# Sheet4.net
KiCad netlist of a schematic drawn in Altium Designer
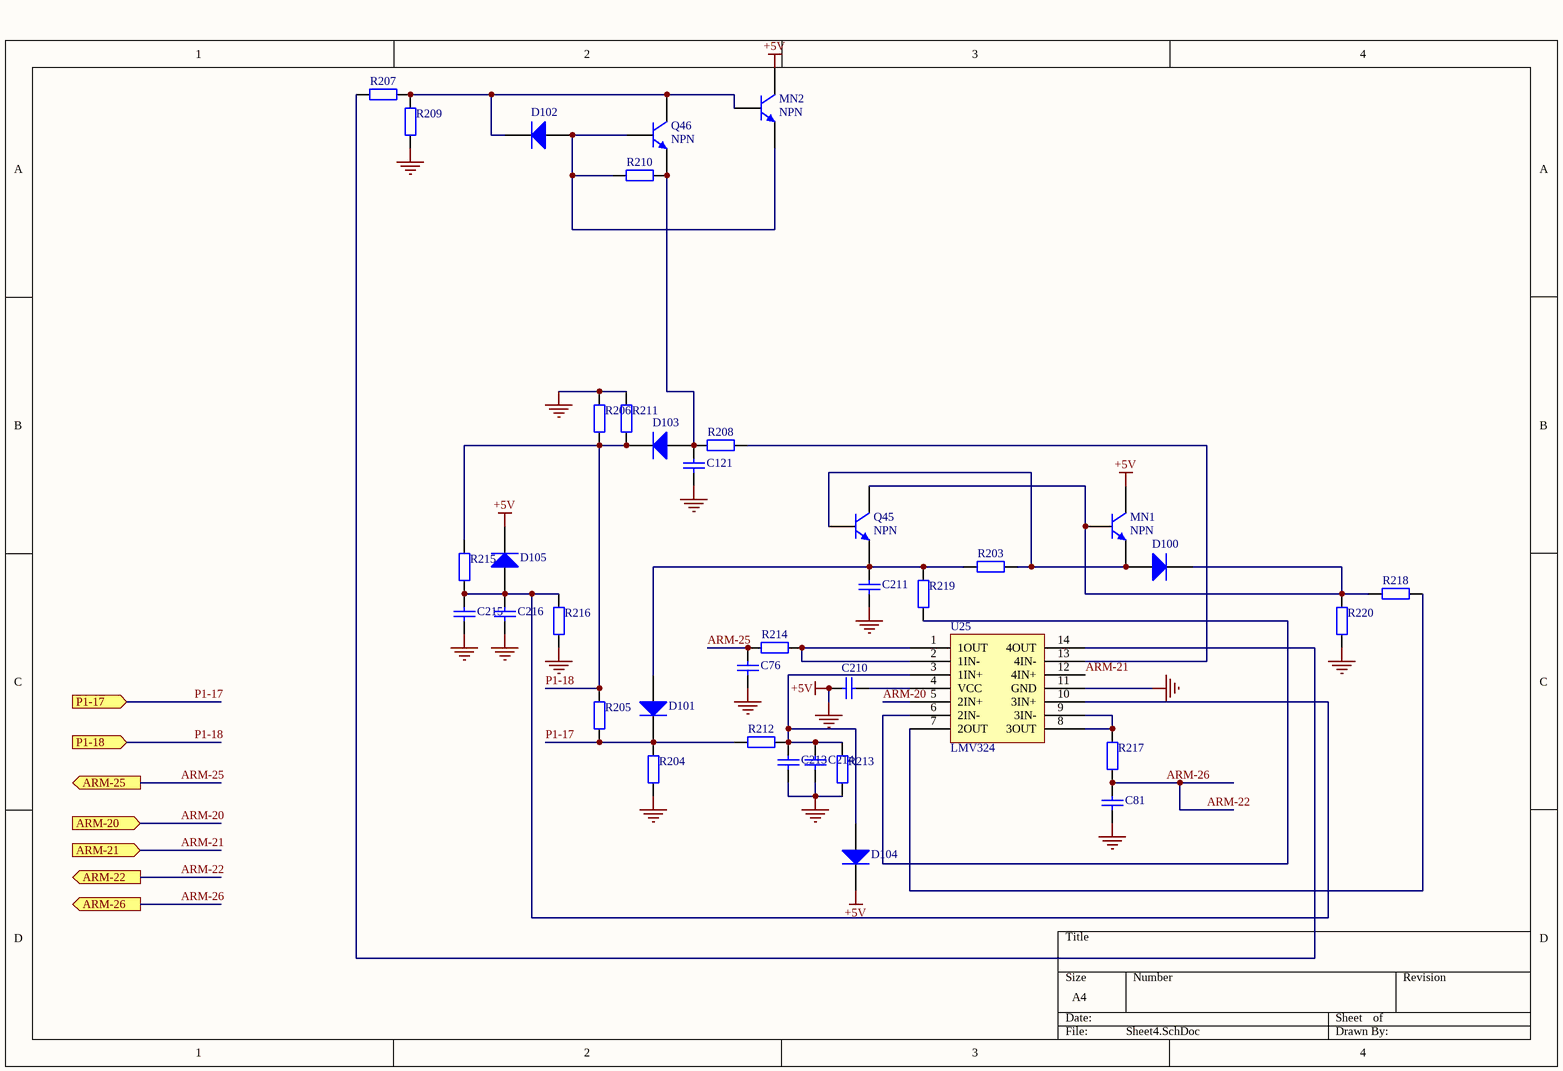
[diagram p0: Sheet4.SchDoc]

(export (version "E")
  (design (tool "Eeschema 10.0.6"))
  (components
    (comp (ref "C76")
      (value "Cap")
      (footprint "RAD-0.3")
      (description "Capacitor")
      (fields (field (name "PUBLISHER") "Altium Limited"))
      (libsource (lib "Miscellaneous Devices") (part "Cap"))
    )
    (comp (ref "C81")
      (value "Cap")
      (footprint "RAD-0.3")
      (description "Capacitor")
      (fields (field (name "PUBLISHER") "Altium Limited"))
      (libsource (lib "Miscellaneous Devices") (part "Cap"))
    )
    (comp (ref "C121")
      (value "Cap")
      (footprint "RAD-0.3")
      (description "Capacitor")
      (fields (field (name "PUBLISHER") "Altium Limited"))
      (libsource (lib "Miscellaneous Devices") (part "Cap"))
    )
    (comp (ref "C210")
      (value "Cap")
      (footprint "RAD-0.3")
      (description "Capacitor")
      (fields (field (name "PUBLISHER") "Altium Limited"))
      (libsource (lib "Miscellaneous Devices") (part "Cap"))
    )
    (comp (ref "C211")
      (value "Cap")
      (footprint "RAD-0.3")
      (description "Capacitor")
      (fields (field (name "PUBLISHER") "Altium Limited"))
      (libsource (lib "Miscellaneous Devices") (part "Cap"))
    )
    (comp (ref "C213")
      (value "Cap")
      (footprint "RAD-0.3")
      (description "Capacitor")
      (fields (field (name "PUBLISHER") "Altium Limited"))
      (libsource (lib "Miscellaneous Devices") (part "Cap"))
    )
    (comp (ref "C214")
      (value "Cap")
      (footprint "RAD-0.3")
      (description "Capacitor")
      (fields (field (name "PUBLISHER") "Altium Limited"))
      (libsource (lib "Miscellaneous Devices") (part "Cap"))
    )
    (comp (ref "C215")
      (value "Cap")
      (footprint "RAD-0.3")
      (description "Capacitor")
      (fields (field (name "PUBLISHER") "Altium Limited"))
      (libsource (lib "Miscellaneous Devices") (part "Cap"))
    )
    (comp (ref "C216")
      (value "Cap")
      (footprint "RAD-0.3")
      (description "Capacitor")
      (fields (field (name "PUBLISHER") "Altium Limited"))
      (libsource (lib "Miscellaneous Devices") (part "Cap"))
    )
    (comp (ref "D100")
      (value "Diode 1N4007")
      (footprint "DO-41")
      (description "1 Amp General Purpose Rectifier")
      (fields (field (name "PUBLISHER") "Altium Limited"))
      (libsource (lib "Miscellaneous Devices") (part "Diode 1N4007"))
    )
    (comp (ref "D101")
      (value "Diode 1N4007")
      (footprint "DO-41")
      (description "1 Amp General Purpose Rectifier")
      (fields (field (name "PUBLISHER") "Altium Limited"))
      (libsource (lib "Miscellaneous Devices") (part "Diode 1N4007"))
    )
    (comp (ref "D102")
      (value "Diode 1N4007")
      (footprint "DO-41")
      (description "1 Amp General Purpose Rectifier")
      (fields (field (name "PUBLISHER") "Altium Limited"))
      (libsource (lib "Miscellaneous Devices") (part "Diode 1N4007"))
    )
    (comp (ref "D103")
      (value "Diode 1N4007")
      (footprint "DO-41")
      (description "1 Amp General Purpose Rectifier")
      (fields (field (name "PUBLISHER") "Altium Limited"))
      (libsource (lib "Miscellaneous Devices") (part "Diode 1N4007"))
    )
    (comp (ref "D104")
      (value "Diode 1N4007")
      (footprint "DO-41")
      (description "1 Amp General Purpose Rectifier")
      (fields (field (name "PUBLISHER") "Altium Limited"))
      (libsource (lib "Miscellaneous Devices") (part "Diode 1N4007"))
    )
    (comp (ref "D105")
      (value "Diode 1N4007")
      (footprint "DO-41")
      (description "1 Amp General Purpose Rectifier")
      (fields (field (name "PUBLISHER") "Altium Limited"))
      (libsource (lib "Miscellaneous Devices") (part "Diode 1N4007"))
    )
    (comp (ref "MN1")
      (value "NPN")
      (footprint "TO-226")
      (description "NPN Bipolar Transistor")
      (fields (field (name "PUBLISHER") "Altium Limited"))
      (libsource (lib "Miscellaneous Devices") (part "NPN"))
    )
    (comp (ref "MN2")
      (value "NPN")
      (footprint "TO-226")
      (description "NPN Bipolar Transistor")
      (fields (field (name "PUBLISHER") "Altium Limited"))
      (libsource (lib "Miscellaneous Devices") (part "NPN"))
    )
    (comp (ref "Q45")
      (value "NPN")
      (footprint "TO-226")
      (description "NPN Bipolar Transistor")
      (fields (field (name "PUBLISHER") "Altium Limited"))
      (libsource (lib "Miscellaneous Devices") (part "NPN"))
    )
    (comp (ref "Q46")
      (value "NPN")
      (footprint "TO-226")
      (description "NPN Bipolar Transistor")
      (fields (field (name "PUBLISHER") "Altium Limited"))
      (libsource (lib "Miscellaneous Devices") (part "NPN"))
    )
    (comp (ref "R203")
      (value "Res2")
      (footprint "AXIAL-0.4")
      (description "Resistor")
      (fields (field (name "PUBLISHER") "Altium Limited"))
      (libsource (lib "") (part "Res2_2"))
    )
    (comp (ref "R204")
      (value "Res2")
      (footprint "AXIAL-0.4")
      (description "Resistor")
      (fields (field (name "PUBLISHER") "Altium Limited"))
      (libsource (lib "Miscellaneous Devices") (part "Res2"))
    )
    (comp (ref "R205")
      (value "Res2")
      (footprint "AXIAL-0.4")
      (description "Resistor")
      (fields (field (name "PUBLISHER") "Altium Limited"))
      (libsource (lib "Miscellaneous Devices") (part "Res2"))
    )
    (comp (ref "R206")
      (value "Res2")
      (footprint "AXIAL-0.4")
      (description "Resistor")
      (fields (field (name "PUBLISHER") "Altium Limited"))
      (libsource (lib "Miscellaneous Devices") (part "Res2"))
    )
    (comp (ref "R207")
      (value "Res2")
      (footprint "AXIAL-0.4")
      (description "Resistor")
      (fields (field (name "PUBLISHER") "Altium Limited"))
      (libsource (lib "") (part "Res2_3"))
    )
    (comp (ref "R208")
      (value "Res2")
      (footprint "AXIAL-0.4")
      (description "Resistor")
      (fields (field (name "PUBLISHER") "Altium Limited"))
      (libsource (lib "") (part "Res2_3"))
    )
    (comp (ref "R209")
      (value "Res2")
      (footprint "AXIAL-0.4")
      (description "Resistor")
      (fields (field (name "PUBLISHER") "Altium Limited"))
      (libsource (lib "") (part "Res2_1"))
    )
    (comp (ref "R210")
      (value "Res2")
      (footprint "AXIAL-0.4")
      (description "Resistor")
      (fields (field (name "PUBLISHER") "Altium Limited"))
      (libsource (lib "") (part "Res2_3"))
    )
    (comp (ref "R211")
      (value "Res2")
      (footprint "AXIAL-0.4")
      (description "Resistor")
      (fields (field (name "PUBLISHER") "Altium Limited"))
      (libsource (lib "Miscellaneous Devices") (part "Res2"))
    )
    (comp (ref "R212")
      (value "Res2")
      (footprint "AXIAL-0.4")
      (description "Resistor")
      (fields (field (name "PUBLISHER") "Altium Limited"))
      (libsource (lib "") (part "Res2_2"))
    )
    (comp (ref "R213")
      (value "Res2")
      (footprint "AXIAL-0.4")
      (description "Resistor")
      (fields (field (name "PUBLISHER") "Altium Limited"))
      (libsource (lib "Miscellaneous Devices") (part "Res2"))
    )
    (comp (ref "R214")
      (value "Res2")
      (footprint "AXIAL-0.4")
      (description "Resistor")
      (fields (field (name "PUBLISHER") "Altium Limited"))
      (libsource (lib "") (part "Res2_2"))
    )
    (comp (ref "R215")
      (value "Res2")
      (footprint "AXIAL-0.4")
      (description "Resistor")
      (fields (field (name "PUBLISHER") "Altium Limited"))
      (libsource (lib "Miscellaneous Devices") (part "Res2"))
    )
    (comp (ref "R216")
      (value "Res2")
      (footprint "AXIAL-0.4")
      (description "Resistor")
      (fields (field (name "PUBLISHER") "Altium Limited"))
      (libsource (lib "Miscellaneous Devices") (part "Res2"))
    )
    (comp (ref "R217")
      (value "Res2")
      (footprint "AXIAL-0.4")
      (description "Resistor")
      (fields (field (name "PUBLISHER") "Altium Limited"))
      (libsource (lib "") (part "Res2_1"))
    )
    (comp (ref "R218")
      (value "Res2")
      (footprint "AXIAL-0.4")
      (description "Resistor")
      (fields (field (name "PUBLISHER") "Altium Limited"))
      (libsource (lib "") (part "Res2_2"))
    )
    (comp (ref "R219")
      (value "Res2")
      (footprint "AXIAL-0.4")
      (description "Resistor")
      (fields (field (name "PUBLISHER") "Altium Limited"))
      (libsource (lib "Miscellaneous Devices") (part "Res2"))
    )
    (comp (ref "R220")
      (value "Res2")
      (footprint "AXIAL-0.4")
      (description "Resistor")
      (fields (field (name "PUBLISHER") "Altium Limited"))
      (libsource (lib "Miscellaneous Devices") (part "Res2"))
    )
    (comp (ref "U25") (value "LMV324") (libsource (lib "LMV324") (part "Component_1")))
  )
  (nets
    (net (code "1") (name "+5V") (class "Default")
      (node (ref "C121") (pin "2") (pinfunction "2_2") (pintype "passive"))
      (node (ref "C210") (pin "2") (pinfunction "2_2") (pintype "passive"))
      (node (ref "C211") (pin "1") (pinfunction "1_1") (pintype "passive"))
      (node (ref "C213") (pin "2") (pinfunction "2_2") (pintype "passive"))
      (node (ref "C214") (pin "2") (pinfunction "2_2") (pintype "passive"))
      (node (ref "C215") (pin "2") (pinfunction "2_2") (pintype "passive"))
      (node (ref "C216") (pin "2") (pinfunction "2_2") (pintype "passive"))
      (node (ref "C76") (pin "1") (pinfunction "1_1") (pintype "passive"))
      (node (ref "C81") (pin "1") (pinfunction "1_1") (pintype "passive"))
      (node (ref "D104") (pin "2") (pinfunction "K_2") (pintype "passive"))
      (node (ref "D105") (pin "2") (pinfunction "K_2") (pintype "passive"))
      (node (ref "MN1") (pin "1") (pinfunction "C_1") (pintype "passive"))
      (node (ref "MN2") (pin "1") (pinfunction "C_1") (pintype "passive"))
      (node (ref "R204") (pin "2") (pinfunction "2_2") (pintype "passive"))
      (node (ref "R206") (pin "1") (pinfunction "1_1") (pintype "passive"))
      (node (ref "R209") (pin "1") (pinfunction "1_1") (pintype "passive"))
      (node (ref "R211") (pin "1") (pinfunction "1_1") (pintype "passive"))
      (node (ref "R213") (pin "2") (pinfunction "2_2") (pintype "passive"))
      (node (ref "R216") (pin "2") (pinfunction "2_2") (pintype "passive"))
      (node (ref "R220") (pin "2") (pinfunction "2_2") (pintype "passive"))
      (node (ref "U25") (pin "11") (pinfunction "GND_11") (pintype "passive"))
    )
    (net (code "2") (name "/ARM-20") (class "Default")
      (node (ref "U25") (pin "5") (pinfunction "2IN+_5") (pintype "passive"))
    )
    (net (code "3") (name "/ARM-21") (class "Default")
      (node (ref "U25") (pin "12") (pinfunction "4IN+_12") (pintype "passive"))
    )
    (net (code "4") (name "/ARM-22") (class "Default")
      (node (ref "C81") (pin "2") (pinfunction "2_2") (pintype "passive"))
      (node (ref "R217") (pin "1") (pinfunction "1_1") (pintype "passive"))
    )
    (net (code "5") (name "/ARM-25") (class "Default")
      (node (ref "C76") (pin "2") (pinfunction "2_2") (pintype "passive"))
      (node (ref "R214") (pin "2") (pinfunction "2_2") (pintype "passive"))
    )
    (net (code "6") (name "/P1-17") (class "Default")
      (node (ref "D101") (pin "2") (pinfunction "K_2") (pintype "passive"))
      (node (ref "R204") (pin "1") (pinfunction "1_1") (pintype "passive"))
      (node (ref "R205") (pin "2") (pinfunction "2_2") (pintype "passive"))
      (node (ref "R212") (pin "2") (pinfunction "2_2") (pintype "passive"))
    )
    (net (code "7") (name "/P1-18") (class "Default")
      (node (ref "D103") (pin "2") (pinfunction "K_2") (pintype "passive"))
      (node (ref "R205") (pin "1") (pinfunction "1_1") (pintype "passive"))
      (node (ref "R206") (pin "2") (pinfunction "2_2") (pintype "passive"))
      (node (ref "R211") (pin "2") (pinfunction "2_2") (pintype "passive"))
      (node (ref "R215") (pin "1") (pinfunction "1_1") (pintype "passive"))
    )
    (net (code "8") (name "Net-(D100-A)") (class "Default")
      (node (ref "D100") (pin "1") (pinfunction "A_1") (pintype "passive"))
      (node (ref "MN1") (pin "3") (pinfunction "E_3") (pintype "passive"))
      (node (ref "Q45") (pin "2") (pinfunction "B_2") (pintype "passive"))
      (node (ref "R203") (pin "1") (pinfunction "1_1") (pintype "passive"))
    )
    (net (code "9") (name "Net-(D100-K)") (class "Default")
      (node (ref "D100") (pin "2") (pinfunction "K_2") (pintype "passive"))
      (node (ref "MN1") (pin "2") (pinfunction "B_2") (pintype "passive"))
      (node (ref "Q45") (pin "1") (pinfunction "C_1") (pintype "passive"))
      (node (ref "R218") (pin "2") (pinfunction "2_2") (pintype "passive"))
      (node (ref "R220") (pin "1") (pinfunction "1_1") (pintype "passive"))
    )
    (net (code "10") (name "Net-(D101-A)") (class "Default")
      (node (ref "C211") (pin "2") (pinfunction "2_2") (pintype "passive"))
      (node (ref "D101") (pin "1") (pinfunction "A_1") (pintype "passive"))
      (node (ref "Q45") (pin "3") (pinfunction "E_3") (pintype "passive"))
      (node (ref "R203") (pin "2") (pinfunction "2_2") (pintype "passive"))
      (node (ref "R219") (pin "1") (pinfunction "1_1") (pintype "passive"))
    )
    (net (code "11") (name "Net-(D102-A)") (class "Default")
      (node (ref "D102") (pin "1") (pinfunction "A_1") (pintype "passive"))
      (node (ref "MN2") (pin "3") (pinfunction "E_3") (pintype "passive"))
      (node (ref "Q46") (pin "2") (pinfunction "B_2") (pintype "passive"))
      (node (ref "R210") (pin "1") (pinfunction "1_1") (pintype "passive"))
    )
    (net (code "12") (name "Net-(D102-K)") (class "Default")
      (node (ref "D102") (pin "2") (pinfunction "K_2") (pintype "passive"))
      (node (ref "MN2") (pin "2") (pinfunction "B_2") (pintype "passive"))
      (node (ref "Q46") (pin "1") (pinfunction "C_1") (pintype "passive"))
      (node (ref "R207") (pin "2") (pinfunction "2_2") (pintype "passive"))
      (node (ref "R209") (pin "2") (pinfunction "2_2") (pintype "passive"))
    )
    (net (code "13") (name "Net-(D103-A)") (class "Default")
      (node (ref "C121") (pin "1") (pinfunction "1_1") (pintype "passive"))
      (node (ref "D103") (pin "1") (pinfunction "A_1") (pintype "passive"))
      (node (ref "Q46") (pin "3") (pinfunction "E_3") (pintype "passive"))
      (node (ref "R208") (pin "1") (pinfunction "1_1") (pintype "passive"))
      (node (ref "R210") (pin "2") (pinfunction "2_2") (pintype "passive"))
    )
    (net (code "14") (name "Net-(D104-A)") (class "Default")
      (node (ref "C213") (pin "1") (pinfunction "1_1") (pintype "passive"))
      (node (ref "C214") (pin "1") (pinfunction "1_1") (pintype "passive"))
      (node (ref "D104") (pin "1") (pinfunction "A_1") (pintype "passive"))
      (node (ref "R212") (pin "1") (pinfunction "1_1") (pintype "passive"))
      (node (ref "R213") (pin "1") (pinfunction "1_1") (pintype "passive"))
      (node (ref "U25") (pin "3") (pinfunction "1IN+_3") (pintype "passive"))
    )
    (net (code "15") (name "Net-(D105-A)") (class "Default")
      (node (ref "C215") (pin "1") (pinfunction "1_1") (pintype "passive"))
      (node (ref "C216") (pin "1") (pinfunction "1_1") (pintype "passive"))
      (node (ref "D105") (pin "1") (pinfunction "A_1") (pintype "passive"))
      (node (ref "R215") (pin "2") (pinfunction "2_2") (pintype "passive"))
      (node (ref "R216") (pin "1") (pinfunction "1_1") (pintype "passive"))
      (node (ref "U25") (pin "10") (pinfunction "3IN+_10") (pintype "passive"))
    )
    (net (code "16") (name "Net-(U25-1IN-)") (class "Default")
      (node (ref "R214") (pin "1") (pinfunction "1_1") (pintype "passive"))
      (node (ref "U25") (pin "1") (pinfunction "1OUT_1") (pintype "passive"))
      (node (ref "U25") (pin "2") (pinfunction "1IN-_2") (pintype "passive"))
    )
    (net (code "17") (name "Net-(U25-2IN-)") (class "Default")
      (node (ref "R219") (pin "2") (pinfunction "2_2") (pintype "passive"))
      (node (ref "U25") (pin "6") (pinfunction "2IN-_6") (pintype "passive"))
    )
    (net (code "18") (name "Net-(U25-2OUT)") (class "Default")
      (node (ref "R218") (pin "1") (pinfunction "1_1") (pintype "passive"))
      (node (ref "U25") (pin "7") (pinfunction "2OUT_7") (pintype "passive"))
    )
    (net (code "19") (name "Net-(U25-3IN-)") (class "Default")
      (node (ref "R217") (pin "2") (pinfunction "2_2") (pintype "passive"))
      (node (ref "U25") (pin "8") (pinfunction "3OUT_8") (pintype "passive"))
      (node (ref "U25") (pin "9") (pinfunction "3IN-_9") (pintype "passive"))
    )
    (net (code "20") (name "Net-(U25-4IN-)") (class "Default")
      (node (ref "R208") (pin "2") (pinfunction "2_2") (pintype "passive"))
      (node (ref "U25") (pin "13") (pinfunction "4IN-_13") (pintype "passive"))
    )
    (net (code "21") (name "Net-(U25-4OUT)") (class "Default")
      (node (ref "R207") (pin "1") (pinfunction "1_1") (pintype "passive"))
      (node (ref "U25") (pin "14") (pinfunction "4OUT_14") (pintype "passive"))
    )
    (net (code "22") (name "Net-(U25-VCC)") (class "Default")
      (node (ref "C210") (pin "1") (pinfunction "1_1") (pintype "passive"))
      (node (ref "U25") (pin "4") (pinfunction "VCC_4") (pintype "passive"))
    )
  )
)
